# Tea_stirrer.net
KiCad netlist of a schematic drawn in EAGLE
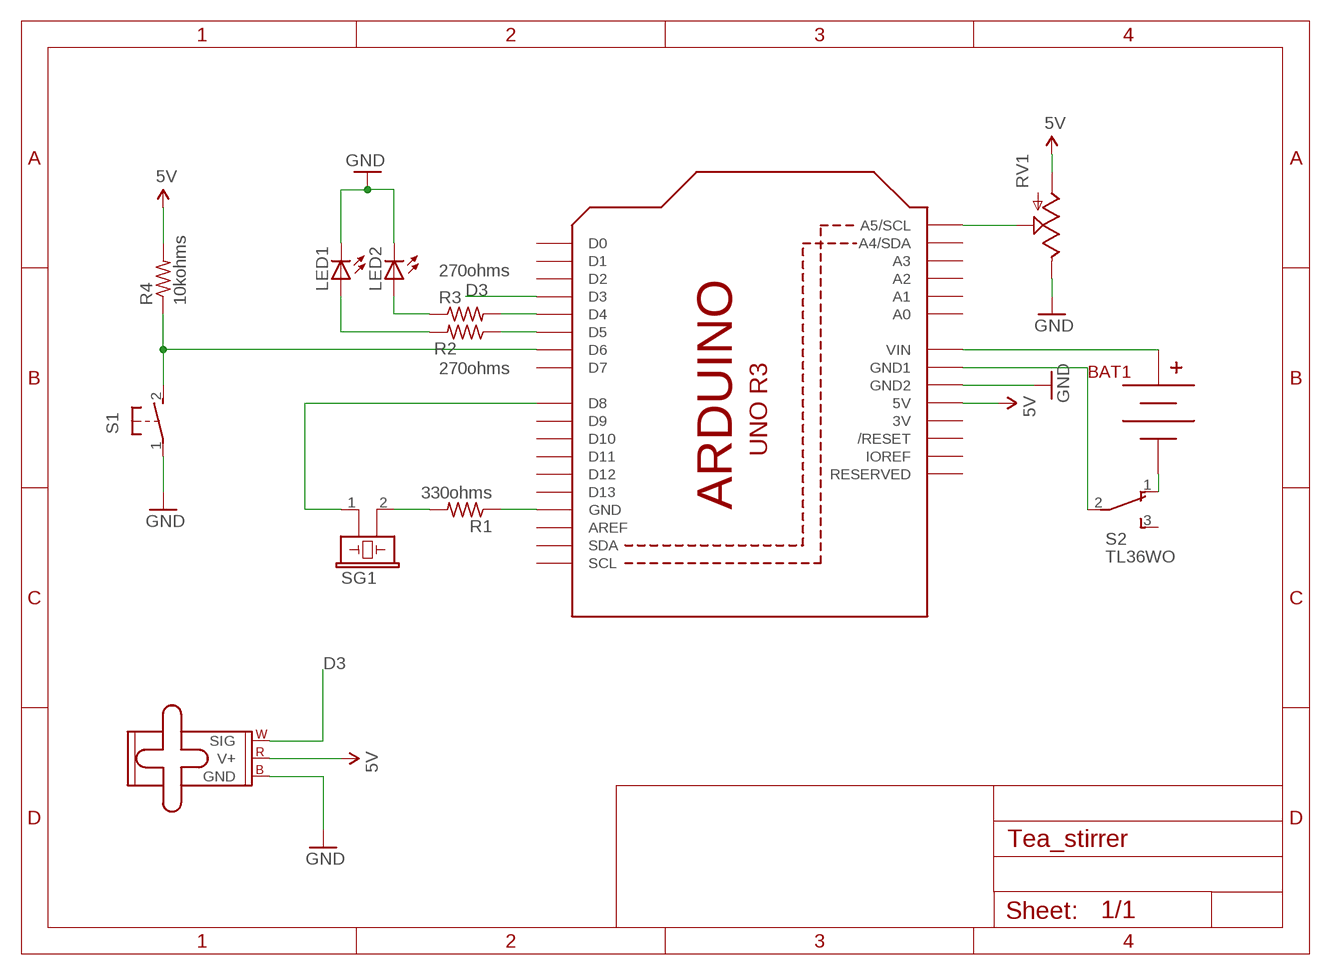
[diagram p0: schematic, sheet 1]

(export (version "E")
  (design (tool "Eeschema 10.0.6"))
  (components
    (comp (ref "BAT1")
      (value "BC9VPC")
      (footprint "eagle-import:BC9VPC")
      (libsource (lib "eagle-import") (part "BC9VPC"))
    )
    (comp (ref "LED1")
      (value "LED5MM")
      (footprint "eagle-import:LED5MM")
      (libsource (lib "eagle-import") (part "LED5MM"))
    )
    (comp (ref "LED2")
      (value "LED5MM")
      (footprint "eagle-import:LED5MM")
      (libsource (lib "eagle-import") (part "LED5MM"))
    )
    (comp (ref "M1")
      (value "SMALL_SERVO")
      (footprint "eagle-import:1X03")
      (libsource (lib "eagle-import") (part "SMALL_SERVO"))
    )
    (comp (ref "R1")
      (value "330ohms")
      (footprint "eagle-import:0805-THM")
      (libsource (lib "eagle-import") (part "FLIPFLOP-RES"))
    )
    (comp (ref "R2")
      (value "270ohms")
      (footprint "eagle-import:0805-THM")
      (libsource (lib "eagle-import") (part "FLIPFLOP-RES"))
    )
    (comp (ref "R3")
      (value "270ohms")
      (footprint "eagle-import:0805-THM")
      (libsource (lib "eagle-import") (part "FLIPFLOP-RES"))
    )
    (comp (ref "R4")
      (value "10kohms")
      (footprint "eagle-import:0805-THM")
      (libsource (lib "eagle-import") (part "FLIPFLOP-RES"))
    )
    (comp (ref "RV1")
      (value "POT")
      (footprint "eagle-import:ALPS_POT")
      (libsource (lib "eagle-import") (part "POT"))
    )
    (comp (ref "S1")
      (value "31-XX")
      (footprint "eagle-import:B3F-31XX")
      (fields (field (name "MPN") "B3F-3100"))
      (libsource (lib "eagle-import") (part "31-XX"))
    )
    (comp (ref "S2")
      (value "TL36WO")
      (footprint "eagle-import:TL3XWO")
      (libsource (lib "eagle-import") (part "TL36WO"))
    )
    (comp (ref "SG1")
      (value "EFBAA40D101")
      (footprint "eagle-import:EFBAA40D101")
      (libsource (lib "eagle-import") (part "EFB?AA40D101"))
    )
    (comp (ref "U2")
      (value "ARDUINOR3-BPLACE")
      (footprint "eagle-import:ARDUINOR3-BPLACE")
      (libsource (lib "eagle-import") (part "ARDUINOR3-BPLACE"))
    )
  )
  (nets
    (net (code "1") (name "/3V") (class "Default")
      (node (ref "U2") (pin "3V") (pinfunction "3V_3V") (pintype "power_in"))
    )
    (net (code "2") (name "/D3") (class "Default")
      (node (ref "M1") (pin "1") (pinfunction "SIG_1") (pintype "bidirectional"))
      (node (ref "U2") (pin "D3") (pinfunction "D3_D3") (pintype "bidirectional"))
    )
    (net (code "3") (name "5V") (class "Default")
      (node (ref "M1") (pin "2") (pinfunction "V+_2") (pintype "bidirectional"))
      (node (ref "R4") (pin "2") (pinfunction "2_2") (pintype "passive"))
      (node (ref "RV1") (pin "P$3") (pinfunction "A_P$3") (pintype "passive"))
      (node (ref "U2") (pin "5V") (pinfunction "5V_5V") (pintype "power_in"))
    )
    (net (code "4") (name "GND") (class "Default")
      (node (ref "LED1") (pin "K") (pinfunction "C_K") (pintype "passive"))
      (node (ref "LED2") (pin "K") (pinfunction "C_K") (pintype "passive"))
      (node (ref "M1") (pin "3") (pinfunction "GND_3") (pintype "bidirectional"))
      (node (ref "RV1") (pin "P$1") (pinfunction "E_P$1") (pintype "passive"))
      (node (ref "S1") (pin "1") (pinfunction "P_1") (pintype "passive"))
      (node (ref "U2") (pin "GND2") (pinfunction "GND2_GND2") (pintype "power_in"))
    )
    (net (code "5") (name "Net-(BAT1-PadV+)") (class "Default")
      (node (ref "BAT1") (pin "V+") (pinfunction "V+_V+") (pintype "bidirectional"))
      (node (ref "U2") (pin "VIN") (pinfunction "VIN_VIN") (pintype "power_in"))
    )
    (net (code "6") (name "Net-(LED1-PadA)") (class "Default")
      (node (ref "LED1") (pin "A") (pinfunction "A_A") (pintype "passive"))
      (node (ref "R2") (pin "2") (pinfunction "2_2") (pintype "passive"))
    )
    (net (code "7") (name "Net-(LED2-PadA)") (class "Default")
      (node (ref "LED2") (pin "A") (pinfunction "A_A") (pintype "passive"))
      (node (ref "R3") (pin "1") (pinfunction "1_1") (pintype "passive"))
    )
    (net (code "8") (name "Net-(R1-Pad1)") (class "Default")
      (node (ref "R1") (pin "1") (pinfunction "1_1") (pintype "passive"))
      (node (ref "U2") (pin "GND") (pinfunction "GND_GND") (pintype "power_in"))
    )
    (net (code "9") (name "Net-(R1-Pad2)") (class "Default")
      (node (ref "R1") (pin "2") (pinfunction "2_2") (pintype "passive"))
      (node (ref "SG1") (pin "2") (pinfunction "2_2") (pintype "passive"))
    )
    (net (code "10") (name "Net-(R2-Pad1)") (class "Default")
      (node (ref "R2") (pin "1") (pinfunction "1_1") (pintype "passive"))
      (node (ref "U2") (pin "D5") (pinfunction "D5_D5") (pintype "bidirectional"))
    )
    (net (code "11") (name "Net-(R3-Pad2)") (class "Default")
      (node (ref "R3") (pin "2") (pinfunction "2_2") (pintype "passive"))
      (node (ref "U2") (pin "D4") (pinfunction "D4_D4") (pintype "bidirectional"))
    )
    (net (code "12") (name "Net-(RV1-S)") (class "Default")
      (node (ref "RV1") (pin "P$2") (pinfunction "S_P$2") (pintype "passive"))
      (node (ref "U2") (pin "A5") (pinfunction "A5/SCL_A5") (pintype "bidirectional"))
    )
    (net (code "13") (name "Net-(S1-S)") (class "Default")
      (node (ref "R4") (pin "1") (pinfunction "1_1") (pintype "passive"))
      (node (ref "S1") (pin "2") (pinfunction "S_2") (pintype "passive"))
      (node (ref "U2") (pin "D6") (pinfunction "D6_D6") (pintype "bidirectional"))
    )
    (net (code "14") (name "Net-(S2-O)") (class "Default")
      (node (ref "BAT1") (pin "V-") (pinfunction "V-_V-") (pintype "bidirectional"))
      (node (ref "S2") (pin "1") (pinfunction "O_1") (pintype "passive"))
    )
    (net (code "15") (name "Net-(S2-P)") (class "Default")
      (node (ref "S2") (pin "2") (pinfunction "P_2") (pintype "passive"))
      (node (ref "U2") (pin "GND1") (pinfunction "GND1_GND1") (pintype "power_in"))
    )
    (net (code "16") (name "Net-(SG1-Pad1)") (class "Default")
      (node (ref "SG1") (pin "1") (pinfunction "1_1") (pintype "passive"))
      (node (ref "U2") (pin "D8") (pinfunction "D8_D8") (pintype "bidirectional"))
    )
    (net (code "17") (name "unconnected-(S2-S-Pad3)") (class "Default")
      (node (ref "S2") (pin "3") (pinfunction "S_3") (pintype "passive"))
    )
    (net (code "18") (name "unconnected-(U2-A4{slash}SDA-PadA4)") (class "Default")
      (node (ref "U2") (pin "A4") (pinfunction "A4/SDA_A4") (pintype "bidirectional"))
    )
    (net (code "19") (name "unconnected-(U2-PadA0)") (class "Default")
      (node (ref "U2") (pin "A0") (pinfunction "A0_A0") (pintype "bidirectional"))
    )
    (net (code "20") (name "unconnected-(U2-PadA1)") (class "Default")
      (node (ref "U2") (pin "A1") (pinfunction "A1_A1") (pintype "bidirectional"))
    )
    (net (code "21") (name "unconnected-(U2-PadA2)") (class "Default")
      (node (ref "U2") (pin "A2") (pinfunction "A2_A2") (pintype "bidirectional"))
    )
    (net (code "22") (name "unconnected-(U2-PadA3)") (class "Default")
      (node (ref "U2") (pin "A3") (pinfunction "A3_A3") (pintype "bidirectional"))
    )
    (net (code "23") (name "unconnected-(U2-PadAREF)") (class "Default")
      (node (ref "U2") (pin "AREF") (pinfunction "AREF_AREF") (pintype "bidirectional"))
    )
    (net (code "24") (name "unconnected-(U2-PadD0)") (class "Default")
      (node (ref "U2") (pin "D0") (pinfunction "D0_D0") (pintype "bidirectional"))
    )
    (net (code "25") (name "unconnected-(U2-PadD1)") (class "Default")
      (node (ref "U2") (pin "D1") (pinfunction "D1_D1") (pintype "bidirectional"))
    )
    (net (code "26") (name "unconnected-(U2-PadD2)") (class "Default")
      (node (ref "U2") (pin "D2") (pinfunction "D2_D2") (pintype "bidirectional"))
    )
    (net (code "27") (name "unconnected-(U2-PadD7)") (class "Default")
      (node (ref "U2") (pin "D7") (pinfunction "D7_D7") (pintype "bidirectional"))
    )
    (net (code "28") (name "unconnected-(U2-PadD9)") (class "Default")
      (node (ref "U2") (pin "D9") (pinfunction "D9_D9") (pintype "bidirectional"))
    )
    (net (code "29") (name "unconnected-(U2-PadD10)") (class "Default")
      (node (ref "U2") (pin "D10") (pinfunction "D10_D10") (pintype "bidirectional"))
    )
    (net (code "30") (name "unconnected-(U2-PadD11)") (class "Default")
      (node (ref "U2") (pin "D11") (pinfunction "D11_D11") (pintype "bidirectional"))
    )
    (net (code "31") (name "unconnected-(U2-PadD12)") (class "Default")
      (node (ref "U2") (pin "D12") (pinfunction "D12_D12") (pintype "bidirectional"))
    )
    (net (code "32") (name "unconnected-(U2-PadD13)") (class "Default")
      (node (ref "U2") (pin "D13") (pinfunction "D13_D13") (pintype "bidirectional"))
    )
    (net (code "33") (name "unconnected-(U2-PadIOREF)") (class "Default")
      (node (ref "U2") (pin "IOREF") (pinfunction "IOREF_IOREF") (pintype "output"))
    )
    (net (code "34") (name "unconnected-(U2-PadRESERVED)") (class "Default")
      (node (ref "U2") (pin "RESERVED") (pinfunction "RESERVED_RESERVED") (pintype "no_connect"))
    )
    (net (code "35") (name "unconnected-(U2-PadSCL)") (class "Default")
      (node (ref "U2") (pin "SCL") (pinfunction "SCL_SCL") (pintype "bidirectional"))
    )
    (net (code "36") (name "unconnected-(U2-PadSDA)") (class "Default")
      (node (ref "U2") (pin "SDA") (pinfunction "SDA_SDA") (pintype "bidirectional"))
    )
    (net (code "37") (name "unconnected-(U2-{slash}RESET-PadRESET)") (class "Default")
      (node (ref "U2") (pin "RESET") (pinfunction "/RESET_RESET") (pintype "bidirectional"))
    )
  )
)
